# RPi_GPS.net
KiCad netlist of a schematic drawn in EAGLE
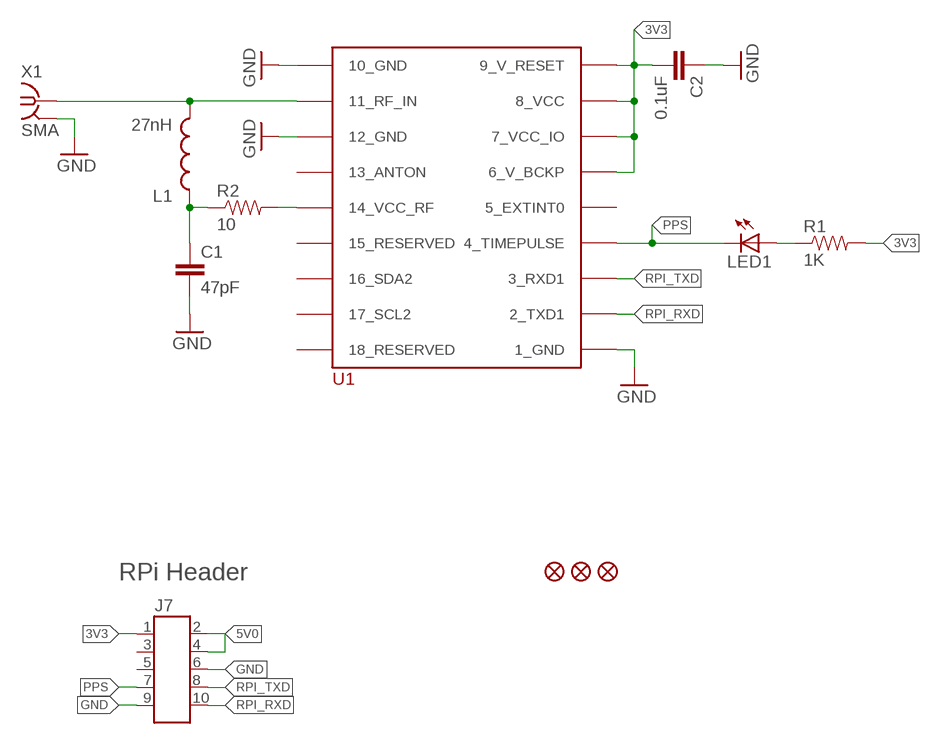
[diagram p0: schematic, sheet 1]

(export (version "E")
  (design (tool "Eeschema 10.0.6"))
  (components
    (comp (ref "C1")
      (value "47pF")
      (footprint "eagle-import:0603-CAP")
      (libsource (lib "eagle-import") (part "CAP0603-CAP"))
    )
    (comp (ref "C2")
      (value "0.1uF")
      (footprint "eagle-import:0603-CAP")
      (libsource (lib "eagle-import") (part "CAP0603-CAP"))
    )
    (comp (ref "FID2")
      (value "FIDUCIAL")
      (footprint "eagle-import:FIDUCIAL")
      (libsource (lib "eagle-import") (part "FIDUCIAL"))
    )
    (comp (ref "FID3")
      (value "FIDUCIAL")
      (footprint "eagle-import:FIDUCIAL")
      (libsource (lib "eagle-import") (part "FIDUCIAL"))
    )
    (comp (ref "FID4")
      (value "FIDUCIAL")
      (footprint "eagle-import:FIDUCIAL")
      (libsource (lib "eagle-import") (part "FIDUCIAL"))
    )
    (comp (ref "J7")
      (value "HEADER-2X5-0.1")
      (footprint "eagle-import:HEADER-2X5")
      (libsource (lib "eagle-import") (part "HEADER-2X5-0.1"))
    )
    (comp (ref "L1")
      (value "27nH")
      (footprint "eagle-import:0603")
      (libsource (lib "eagle-import") (part "INDUCTOR0603"))
    )
    (comp (ref "LED1")
      (value "LED0603")
      (footprint "eagle-import:LED-0603")
      (libsource (lib "eagle-import") (part "LED0603"))
    )
    (comp (ref "R1")
      (value "1K")
      (footprint "eagle-import:0603-RES")
      (libsource (lib "eagle-import") (part "RESISTOR0603-RES"))
    )
    (comp (ref "R2")
      (value "10")
      (footprint "eagle-import:0603-RES")
      (libsource (lib "eagle-import") (part "RESISTOR0603-RES"))
    )
    (comp (ref "U1")
      (value "UBLOX_MAX")
      (footprint "eagle-import:UBLOX_MAX")
      (libsource (lib "eagle-import") (part "UBLOX_MAX"))
    )
    (comp (ref "X1")
      (value "SMA")
      (footprint "eagle-import:SMA_EDGE")
      (libsource (lib "eagle-import") (part "SMA"))
    )
  )
  (nets
    (net (code "1") (name "3V3") (class "Default")
      (node (ref "C2") (pin "2") (pinfunction "2_2") (pintype "passive"))
      (node (ref "J7") (pin "1") (pinfunction "1_1") (pintype "bidirectional"))
      (node (ref "R1") (pin "2") (pinfunction "2_2") (pintype "passive"))
      (node (ref "U1") (pin "6_V_BCKP") (pinfunction "6_V_BCKP_6_V_BCKP") (pintype "bidirectional"))
      (node (ref "U1") (pin "7_VCC_IO") (pinfunction "7_VCC_IO_7_VCC_IO") (pintype "power_in"))
      (node (ref "U1") (pin "8_VCC") (pinfunction "8_VCC_8_VCC") (pintype "power_in"))
      (node (ref "U1") (pin "9_V_RESET") (pinfunction "9_V_RESET_9_V_RESET") (pintype "power_in"))
    )
    (net (code "2") (name "5V0") (class "Default")
      (node (ref "J7") (pin "2") (pinfunction "2_2") (pintype "bidirectional"))
      (node (ref "J7") (pin "4") (pinfunction "4_4") (pintype "bidirectional"))
    )
    (net (code "3") (name "GND") (class "Default")
      (node (ref "C1") (pin "2") (pinfunction "2_2") (pintype "passive"))
      (node (ref "C2") (pin "1") (pinfunction "1_1") (pintype "passive"))
      (node (ref "J7") (pin "6") (pinfunction "6_6") (pintype "bidirectional"))
      (node (ref "J7") (pin "9") (pinfunction "9_9") (pintype "bidirectional"))
      (node (ref "U1") (pin "10_GND") (pinfunction "10_GND_10_GND") (pintype "power_in"))
      (node (ref "U1") (pin "12_GND") (pinfunction "12_GND_12_GND") (pintype "power_in"))
      (node (ref "U1") (pin "1_GND") (pinfunction "1_GND_1_GND") (pintype "power_in"))
      (node (ref "X1") (pin "GND@1") (pinfunction "2_GND@1") (pintype "passive"))
      (node (ref "X1") (pin "GND@2") (pinfunction "2_GND@2") (pintype "passive"))
      (node (ref "X1") (pin "GND@3") (pinfunction "2_GND@3") (pintype "passive"))
      (node (ref "X1") (pin "GND@4") (pinfunction "2_GND@4") (pintype "passive"))
    )
    (net (code "4") (name "Net-(C1-Pad1)") (class "Default")
      (node (ref "C1") (pin "1") (pinfunction "1_1") (pintype "passive"))
      (node (ref "L1") (pin "1") (pinfunction "1_1") (pintype "passive"))
      (node (ref "R2") (pin "1") (pinfunction "1_1") (pintype "passive"))
    )
    (net (code "5") (name "Net-(LED1-PadA)") (class "Default")
      (node (ref "LED1") (pin "A") (pinfunction "A_A") (pintype "passive"))
      (node (ref "R1") (pin "1") (pinfunction "1_1") (pintype "passive"))
    )
    (net (code "6") (name "Net-(R2-Pad2)") (class "Default")
      (node (ref "R2") (pin "2") (pinfunction "2_2") (pintype "passive"))
      (node (ref "U1") (pin "14_VCC_RF") (pinfunction "14_VCC_RF_14_VCC_RF") (pintype "bidirectional"))
    )
    (net (code "7") (name "Net-(X1-1)") (class "Default")
      (node (ref "L1") (pin "2") (pinfunction "2_2") (pintype "passive"))
      (node (ref "U1") (pin "11_RF_IN") (pinfunction "11_RF_IN_11_RF_IN") (pintype "bidirectional"))
      (node (ref "X1") (pin "SIG") (pinfunction "1_SIG") (pintype "passive"))
    )
    (net (code "8") (name "PPS") (class "Default")
      (node (ref "J7") (pin "7") (pinfunction "7_7") (pintype "bidirectional"))
      (node (ref "LED1") (pin "C") (pinfunction "C_C") (pintype "passive"))
      (node (ref "U1") (pin "4_TIMEPULSE") (pinfunction "4_TIMEPULSE_4_TIMEPULSE") (pintype "bidirectional"))
    )
    (net (code "9") (name "RPI_RXD") (class "Default")
      (node (ref "J7") (pin "10") (pinfunction "10_10") (pintype "bidirectional"))
      (node (ref "U1") (pin "2_TXD1") (pinfunction "2_TXD1_2_TXD1") (pintype "bidirectional"))
    )
    (net (code "10") (name "RPI_TXD") (class "Default")
      (node (ref "J7") (pin "8") (pinfunction "8_8") (pintype "bidirectional"))
      (node (ref "U1") (pin "3_RXD1") (pinfunction "3_RXD1_3_RXD1") (pintype "bidirectional"))
    )
    (net (code "11") (name "unconnected-(J7-Pad3)") (class "Default")
      (node (ref "J7") (pin "3") (pinfunction "3_3") (pintype "bidirectional"))
    )
    (net (code "12") (name "unconnected-(J7-Pad5)") (class "Default")
      (node (ref "J7") (pin "5") (pinfunction "5_5") (pintype "bidirectional"))
    )
    (net (code "13") (name "unconnected-(U1-Pad5_EXTINT0)") (class "Default")
      (node (ref "U1") (pin "5_EXTINT0") (pinfunction "5_EXTINT0_5_EXTINT0") (pintype "bidirectional"))
    )
    (net (code "14") (name "unconnected-(U1-Pad13_ANTON)") (class "Default")
      (node (ref "U1") (pin "13_ANTON") (pinfunction "13_ANTON_13_ANTON") (pintype "bidirectional"))
    )
    (net (code "15") (name "unconnected-(U1-Pad15_RESERVED)") (class "Default")
      (node (ref "U1") (pin "15_RESERVED") (pinfunction "15_RESERVED_15_RESERVED") (pintype "bidirectional"))
    )
    (net (code "16") (name "unconnected-(U1-Pad16_SDA2)") (class "Default")
      (node (ref "U1") (pin "16_SDA2") (pinfunction "16_SDA2_16_SDA2") (pintype "bidirectional"))
    )
    (net (code "17") (name "unconnected-(U1-Pad17_SCL2)") (class "Default")
      (node (ref "U1") (pin "17_SCL2") (pinfunction "17_SCL2_17_SCL2") (pintype "bidirectional"))
    )
    (net (code "18") (name "unconnected-(U1-Pad18_RESERVED)") (class "Default")
      (node (ref "U1") (pin "18_RESERVED") (pinfunction "18_RESERVED_18_RESERVED") (pintype "bidirectional"))
    )
  )
)
